# Power_Distribution_-_Solar_Sense_Telemet.net
KiCad netlist of a schematic drawn in Altium Designer
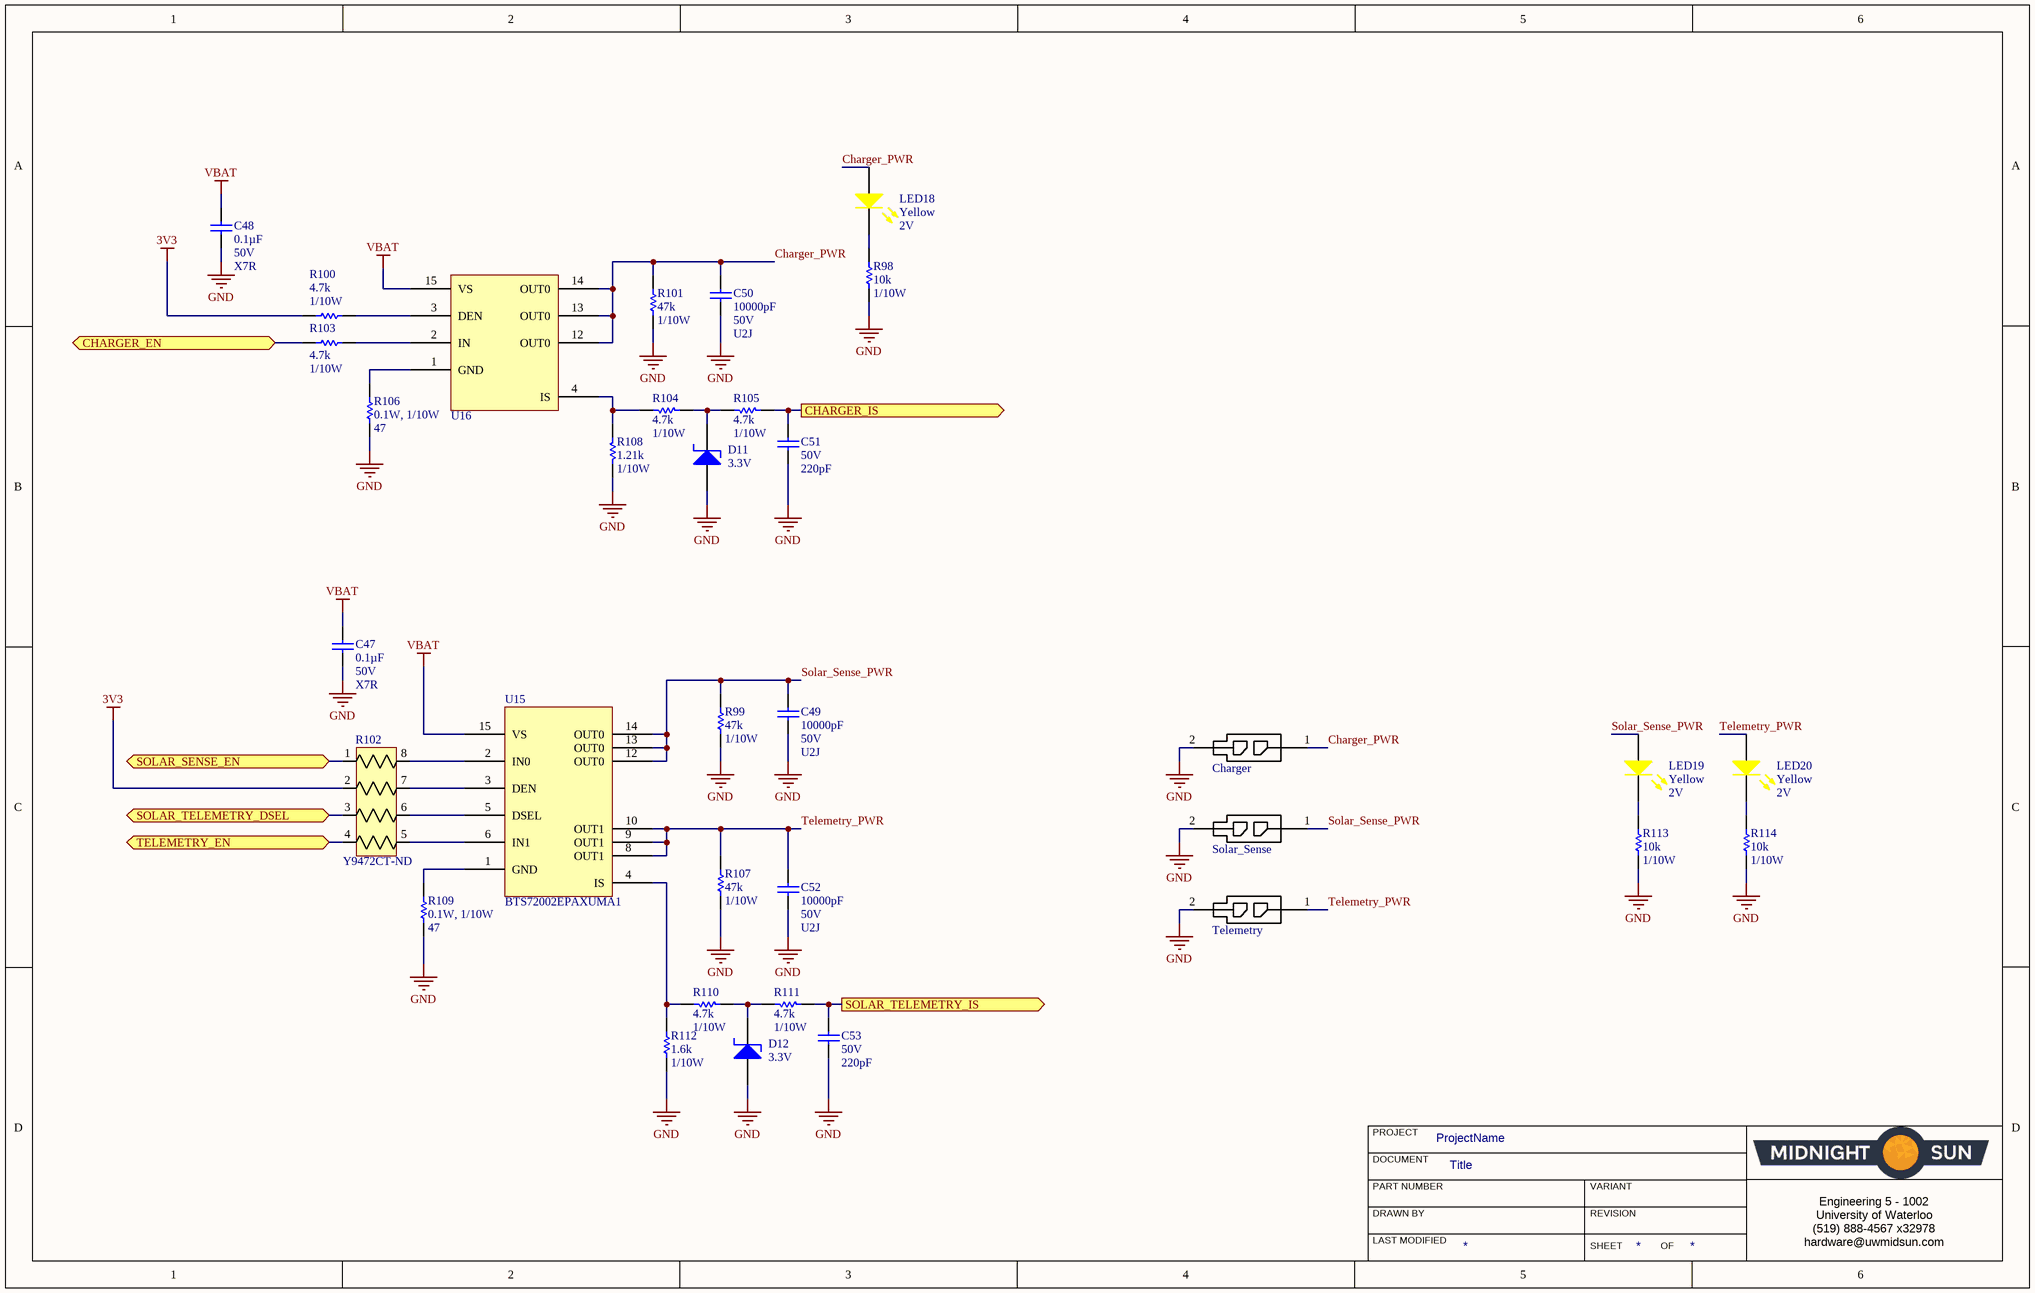
[diagram p0: Power Distribution - Solar Sense, Telemetry, and Charger.SchDoc]

(export (version "E")
  (design (tool "Eeschema 10.0.6"))
  (components
    (comp (ref "C47")
      (value "CAP CER 0.1UF 50V 10% X7R 0603")
      (footprint "CAP, 0603")
      (description "0.10µF ±10% 50V Ceramic Capacitor X7R 0603 (1608 Metric)")
      (fields
        (field (name "TOLERANCE") "±10%")
        (field (name "CAPACITANCE") "0.1µF")
        (field (name "VOLTAGE") "50V")
        (field (name "TEMPERATURE COEFFICIENT") "X7R")
      )
      (libsource (lib "Schematic Diagrams") (part "CAP CER 0.1UF 50V 10% X7R 0603"))
    )
    (comp (ref "C48")
      (value "CAP CER 0.1UF 50V 10% X7R 0603")
      (footprint "CAP, 0603")
      (description "0.10µF ±10% 50V Ceramic Capacitor X7R 0603 (1608 Metric)")
      (fields
        (field (name "TOLERANCE") "±10%")
        (field (name "CAPACITANCE") "0.1µF")
        (field (name "VOLTAGE") "50V")
        (field (name "TEMPERATURE COEFFICIENT") "X7R")
      )
      (libsource (lib "Schematic Diagrams") (part "CAP CER 0.1UF 50V 10% X7R 0603"))
    )
    (comp (ref "C49")
      (value "CAP CER 10nF 50V 5% X7R 0603")
      (footprint "CAP, 0603")
      (description "10000pF ±5% 50V Ceramic Capacitor U2J 0603 (1608 Metric)")
      (fields
        (field (name "TOLERANCE") "±5%")
        (field (name "CAPACITANCE") "10000pF")
        (field (name "VOLTAGE") "50V")
        (field (name "TEMPERATURE COEFFICIENT") "U2J")
      )
      (libsource (lib "Schematic Diagrams") (part "CAP CER 10nF 50V 5% X7R 0603"))
    )
    (comp (ref "C50")
      (value "CAP CER 10nF 50V 5% X7R 0603")
      (footprint "CAP, 0603")
      (description "10000pF ±5% 50V Ceramic Capacitor U2J 0603 (1608 Metric)")
      (fields
        (field (name "TOLERANCE") "±5%")
        (field (name "CAPACITANCE") "10000pF")
        (field (name "VOLTAGE") "50V")
        (field (name "TEMPERATURE COEFFICIENT") "U2J")
      )
      (libsource (lib "Schematic Diagrams") (part "CAP CER 10nF 50V 5% X7R 0603"))
    )
    (comp (ref "C51")
      (value "CAP CER 220PF 50V C0G/NP0 0603")
      (footprint "CAP, 0603")
      (description "220pF ±5% 50V Ceramic Capacitor C0G, NP0 0603 (1608 Metric)")
      (fields
        (field (name "MANUFACTURER") "KEMET")
        (field (name "TOLERANCE") "5%")
        (field (name "VOLTAGE RATING") "50V")
        (field (name "CAPACITANCE") "220pF")
      )
      (libsource (lib "Schematic Diagrams") (part "CAP CER 220PF 50V C0G/NP0 0603"))
    )
    (comp (ref "C52")
      (value "CAP CER 10nF 50V 5% X7R 0603")
      (footprint "CAP, 0603")
      (description "10000pF ±5% 50V Ceramic Capacitor U2J 0603 (1608 Metric)")
      (fields
        (field (name "TOLERANCE") "±5%")
        (field (name "CAPACITANCE") "10000pF")
        (field (name "VOLTAGE") "50V")
        (field (name "TEMPERATURE COEFFICIENT") "U2J")
      )
      (libsource (lib "Schematic Diagrams") (part "CAP CER 10nF 50V 5% X7R 0603"))
    )
    (comp (ref "C53")
      (value "CAP CER 220PF 50V C0G/NP0 0603")
      (footprint "CAP, 0603")
      (description "220pF ±5% 50V Ceramic Capacitor C0G, NP0 0603 (1608 Metric)")
      (fields
        (field (name "MANUFACTURER") "KEMET")
        (field (name "TOLERANCE") "5%")
        (field (name "VOLTAGE RATING") "50V")
        (field (name "CAPACITANCE") "220pF")
      )
      (libsource (lib "Schematic Diagrams") (part "CAP CER 220PF 50V C0G/NP0 0603"))
    )
    (comp (ref "Charger")
      (value "CONN 2POS MICRO-FIT 3mm")
      (footprint "CONN, 2POS MICRO-FIT")
      (description "Connector Header Through Hole 2 position")
      (fields (field (name "MANUFACTURER") "Molex") (field (name "MANUFACTURER PART NUMBER") "43045-0227"))
      (libsource (lib "Schematic Diagrams") (part "CONN 2POS MICRO-FIT 3mm"))
    )
    (comp (ref "D11")
      (value "DIODE ZENER 3.3V 200MW SOD323")
      (footprint "sod-323")
      (description "Zener Diode 3.3V 200mW ±5% Surface Mount SOD-323")
      (fields (field (name "VOLTAGE") "3.3V"))
      (libsource (lib "Schematic Diagrams") (part "DIODE ZENER 3.3V 200MW SOD323"))
    )
    (comp (ref "D12")
      (value "DIODE ZENER 3.3V 200MW SOD323")
      (footprint "sod-323")
      (description "Zener Diode 3.3V 200mW ±5% Surface Mount SOD-323")
      (fields (field (name "VOLTAGE") "3.3V"))
      (libsource (lib "Schematic Diagrams") (part "DIODE ZENER 3.3V 200MW SOD323"))
    )
    (comp (ref "LED18")
      (value "LED YELLOW CLEAR 2.1V 0603")
      (footprint "LED_0603")
      (description "Yellow 590nm LED Indication - Discrete 2V 0603 (1608 Metric)")
      (fields
        (field (name "MANUFACTURER") "Wurth Electronics Inc.")
        (field (name "MANUFACTURER PART NUMBER") "150060YS75000")
        (field (name "COLOR") "Yellow")
        (field (name "VOLTAGE - FORWARD (VF) (TYP)") "2V")
      )
      (libsource (lib "Schematic Diagrams") (part "LED YELLOW CLEAR 2.1V 0603"))
    )
    (comp (ref "LED19")
      (value "LED YELLOW CLEAR 2.1V 0603")
      (footprint "LED_0603")
      (description "Yellow 590nm LED Indication - Discrete 2V 0603 (1608 Metric)")
      (fields
        (field (name "MANUFACTURER") "Wurth Electronics Inc.")
        (field (name "MANUFACTURER PART NUMBER") "150060YS75000")
        (field (name "COLOR") "Yellow")
        (field (name "VOLTAGE - FORWARD (VF) (TYP)") "2V")
      )
      (libsource (lib "Schematic Diagrams") (part "LED YELLOW CLEAR 2.1V 0603"))
    )
    (comp (ref "LED20")
      (value "LED YELLOW CLEAR 2.1V 0603")
      (footprint "LED_0603")
      (description "Yellow 590nm LED Indication - Discrete 2V 0603 (1608 Metric)")
      (fields
        (field (name "MANUFACTURER") "Wurth Electronics Inc.")
        (field (name "MANUFACTURER PART NUMBER") "150060YS75000")
        (field (name "COLOR") "Yellow")
        (field (name "VOLTAGE - FORWARD (VF) (TYP)") "2V")
      )
      (libsource (lib "Schematic Diagrams") (part "LED YELLOW CLEAR 2.1V 0603"))
    )
    (comp (ref "R98")
      (value "RES 10K OHM 1% 1/10W 0603")
      (footprint "RES, 0603")
      (description "RES SMD 10K OHM 1% 1/10W 0603")
      (fields
        (field (name "TOLERANCE") "±1%")
        (field (name "RESISTANCE") "10k")
        (field (name "POWER") "1/10W")
      )
      (libsource (lib "Schematic Diagrams") (part "RES 10K OHM 1% 1/10W 0603"))
    )
    (comp (ref "R99")
      (value "RES 47K OHM 1% 1/10W 0603")
      (footprint "RES, 0603")
      (description "47 kOhms ±1% 0.1W, 1/10W Chip Resistor 0603 (1608 Metric) Automotive AEC-Q200 Thick Film")
      (fields
        (field (name "MANUFACTURER") "Panasonic")
        (field (name "MANUFACTURER PART NUMBER") "ERJ3EKF4702V")
        (field (name "RESISTANCE") "47k")
        (field (name "POWER RATING") "1/10W")
      )
      (libsource (lib "Schematic Diagrams") (part "RES 47K OHM 1% 1/10W 0603"))
    )
    (comp (ref "R100")
      (value "RES 4.7K OHM 1% 1/10W 0603")
      (footprint "RES, 0603")
      (description "4.7k Ohm ±1% 0.1W, 1/10W Chip Resistor 0603 (1608 Metric) Moisture Resistant Thick Film")
      (fields
        (field (name "TOLERANCE") "±1%")
        (field (name "RESISTANCE (OHMS)") "4.7k")
        (field (name "POWER (WATTS)") "1/10W")
      )
      (libsource (lib "Schematic Diagrams") (part "RES 4.7K OHM 1% 1/10W 0603"))
    )
    (comp (ref "R101")
      (value "RES 47K OHM 1% 1/10W 0603")
      (footprint "RES, 0603")
      (description "47 kOhms ±1% 0.1W, 1/10W Chip Resistor 0603 (1608 Metric) Automotive AEC-Q200 Thick Film")
      (fields
        (field (name "MANUFACTURER") "Panasonic")
        (field (name "MANUFACTURER PART NUMBER") "ERJ3EKF4702V")
        (field (name "RESISTANCE") "47k")
        (field (name "POWER RATING") "1/10W")
      )
      (libsource (lib "Schematic Diagrams") (part "RES 47K OHM 1% 1/10W 0603"))
    )
    (comp (ref "R102")
      (value "RES ARRAY 4 RES 4.7K OHM 1206")
      (footprint "RES ARRAY 4RES 1206")
      (fields (field (name "TOLERANCE") "±5%") (field (name "SUPPLIER PART NUMBER 1") "Y9472CT-ND"))
      (libsource (lib "Schematic Diagrams") (part "RES ARRAY 4 RES 4.7K OHM 1206"))
    )
    (comp (ref "R103")
      (value "RES 4.7K OHM 1% 1/10W 0603")
      (footprint "RES, 0603")
      (description "4.7k Ohm ±1% 0.1W, 1/10W Chip Resistor 0603 (1608 Metric) Moisture Resistant Thick Film")
      (fields
        (field (name "TOLERANCE") "±1%")
        (field (name "RESISTANCE (OHMS)") "4.7k")
        (field (name "POWER (WATTS)") "1/10W")
      )
      (libsource (lib "Schematic Diagrams") (part "RES 4.7K OHM 1% 1/10W 0603"))
    )
    (comp (ref "R104")
      (value "RES 4.7K OHM 1% 1/10W 0603")
      (footprint "RES, 0603")
      (description "4.7k Ohm ±1% 0.1W, 1/10W Chip Resistor 0603 (1608 Metric) Moisture Resistant Thick Film")
      (fields
        (field (name "TOLERANCE") "±1%")
        (field (name "RESISTANCE (OHMS)") "4.7k")
        (field (name "POWER (WATTS)") "1/10W")
      )
      (libsource (lib "Schematic Diagrams") (part "RES 4.7K OHM 1% 1/10W 0603"))
    )
    (comp (ref "R105")
      (value "RES 4.7K OHM 1% 1/10W 0603")
      (footprint "RES, 0603")
      (description "4.7k Ohm ±1% 0.1W, 1/10W Chip Resistor 0603 (1608 Metric) Moisture Resistant Thick Film")
      (fields
        (field (name "TOLERANCE") "±1%")
        (field (name "RESISTANCE (OHMS)") "4.7k")
        (field (name "POWER (WATTS)") "1/10W")
      )
      (libsource (lib "Schematic Diagrams") (part "RES 4.7K OHM 1% 1/10W 0603"))
    )
    (comp (ref "R106")
      (value "RES SMD 47 OHM 1% 1/10W 0603")
      (footprint "RES, 0603")
      (fields
        (field (name "TOLERANCE") "±1%")
        (field (name "POWER (WATTS)") "0.1W, 1/10W")
        (field (name "VALUES") "47")
      )
      (libsource (lib "Schematic Diagrams") (part "RES SMD 47 OHM 1% 1/10W 0603"))
    )
    (comp (ref "R107")
      (value "RES 47K OHM 1% 1/10W 0603")
      (footprint "RES, 0603")
      (description "47 kOhms ±1% 0.1W, 1/10W Chip Resistor 0603 (1608 Metric) Automotive AEC-Q200 Thick Film")
      (fields
        (field (name "MANUFACTURER") "Panasonic")
        (field (name "MANUFACTURER PART NUMBER") "ERJ3EKF4702V")
        (field (name "RESISTANCE") "47k")
        (field (name "POWER RATING") "1/10W")
      )
      (libsource (lib "Schematic Diagrams") (part "RES 47K OHM 1% 1/10W 0603"))
    )
    (comp (ref "R108")
      (value "RES 1.21K OHM 1% 1/10W 0603")
      (footprint "RES, 0603")
      (description "1.21k Ohm ±1% 0.1W, 1/10W Chip Resistor 0603 (1608 Metric) Moisture Resistant Thick Film")
      (fields
        (field (name "TOLERANCE") "±1%")
        (field (name "RESISTANCE") "1.21k")
        (field (name "POWER") "1/10W")
      )
      (libsource (lib "Schematic Diagrams") (part "RES 1.21K OHM 1% 1/10W 0603"))
    )
    (comp (ref "R109")
      (value "RES SMD 47 OHM 1% 1/10W 0603")
      (footprint "RES, 0603")
      (fields
        (field (name "TOLERANCE") "±1%")
        (field (name "POWER (WATTS)") "0.1W, 1/10W")
        (field (name "VALUES") "47")
      )
      (libsource (lib "Schematic Diagrams") (part "RES SMD 47 OHM 1% 1/10W 0603"))
    )
    (comp (ref "R110")
      (value "RES 4.7K OHM 1% 1/10W 0603")
      (footprint "RES, 0603")
      (description "4.7k Ohm ±1% 0.1W, 1/10W Chip Resistor 0603 (1608 Metric) Moisture Resistant Thick Film")
      (fields
        (field (name "TOLERANCE") "±1%")
        (field (name "RESISTANCE (OHMS)") "4.7k")
        (field (name "POWER (WATTS)") "1/10W")
      )
      (libsource (lib "Schematic Diagrams") (part "RES 4.7K OHM 1% 1/10W 0603"))
    )
    (comp (ref "R111")
      (value "RES 4.7K OHM 1% 1/10W 0603")
      (footprint "RES, 0603")
      (description "4.7k Ohm ±1% 0.1W, 1/10W Chip Resistor 0603 (1608 Metric) Moisture Resistant Thick Film")
      (fields
        (field (name "TOLERANCE") "±1%")
        (field (name "RESISTANCE (OHMS)") "4.7k")
        (field (name "POWER (WATTS)") "1/10W")
      )
      (libsource (lib "Schematic Diagrams") (part "RES 4.7K OHM 1% 1/10W 0603"))
    )
    (comp (ref "R112")
      (value "RES 1.6K OHM 1% 1/10W 0603")
      (footprint "RES, 0603")
      (description "1.6 kOhms ±1% 0.1W, 1/10W Chip Resistor 0603 (1608 Metric) Moisture Resistant Thick Film")
      (fields
        (field (name "MANUFACTURER") "Yageo")
        (field (name "MANUFACTURER PART NUMBER") "RC0603FR-071K6L")
        (field (name "RESISTANCE") "1.6k")
        (field (name "POWER RATING") "1/10W")
      )
      (libsource (lib "Schematic Diagrams") (part "RES 1.6K OHM 1% 1/10W 0603"))
    )
    (comp (ref "R113")
      (value "RES 10K OHM 1% 1/10W 0603")
      (footprint "RES, 0603")
      (description "RES SMD 10K OHM 1% 1/10W 0603")
      (fields
        (field (name "TOLERANCE") "±1%")
        (field (name "RESISTANCE") "10k")
        (field (name "POWER") "1/10W")
      )
      (libsource (lib "Schematic Diagrams") (part "RES 10K OHM 1% 1/10W 0603"))
    )
    (comp (ref "R114")
      (value "RES 10K OHM 1% 1/10W 0603")
      (footprint "RES, 0603")
      (description "RES SMD 10K OHM 1% 1/10W 0603")
      (fields
        (field (name "TOLERANCE") "±1%")
        (field (name "RESISTANCE") "10k")
        (field (name "POWER") "1/10W")
      )
      (libsource (lib "Schematic Diagrams") (part "RES 10K OHM 1% 1/10W 0603"))
    )
    (comp (ref "Solar_Sense")
      (value "CONN 2POS MICRO-FIT 3mm")
      (footprint "CONN, 2POS MICRO-FIT")
      (description "Connector Header Through Hole 2 position")
      (fields (field (name "MANUFACTURER") "Molex") (field (name "MANUFACTURER PART NUMBER") "43045-0227"))
      (libsource (lib "Schematic Diagrams") (part "CONN 2POS MICRO-FIT 3mm"))
    )
    (comp (ref "Telemetry")
      (value "CONN 2POS MICRO-FIT 3mm")
      (footprint "CONN, 2POS MICRO-FIT")
      (description "Connector Header Through Hole 2 position")
      (fields (field (name "MANUFACTURER") "Molex") (field (name "MANUFACTURER PART NUMBER") "43045-0227"))
      (libsource (lib "Schematic Diagrams") (part "CONN 2POS MICRO-FIT 3mm"))
    )
    (comp (ref "U15")
      (value "IC LOAD SWITCH BTS7200-2EPA PG-TSDSO-14_1")
      (footprint "IC LOAD SWITCH PG-TSDSO-14-22")
      (description "Power Switch/Driver 1:1 N-Channel 1.2A PG-TSDSO-14-22")
      (fields
        (field (name "MANUFACTURER") "Infineon")
        (field (name "MANUFACTURER PART NUMBER") "BTS72002EPAXUMA1")
      )
      (libsource (lib "Schematic Diagrams") (part "IC LOAD SWITCH BTS7200-2EPA PG-TSDSO-14_1"))
    )
    (comp (ref "U16")
      (value "IC LOAD SWITCH BTS70401EPA PG-TSDSO-14-22")
      (footprint "IC LOAD SWITCH PG-TSDSO-14-22")
      (description "Power Switch/Driver 1:1 N-Channel 4.5A PG-TSDSO-14-22")
      (fields
        (field (name "MANUFACTURER") "Infineon")
        (field (name "MANUFACTURER PART NUMBER") "BTS70401EPAXUMA1")
      )
      (libsource (lib "Schematic Diagrams") (part "IC LOAD SWITCH BTS70401EPA PG-TSDSO-14-22"))
    )
  )
  (nets
    (net (code "1") (name "/CHARGER_EN") (class "Default")
      (node (ref "R103") (pin "1") (pinfunction "1_1") (pintype "passive"))
    )
    (net (code "2") (name "/CHARGER_IS") (class "Default")
      (node (ref "C51") (pin "1") (pinfunction "1_1") (pintype "passive"))
      (node (ref "R105") (pin "1") (pinfunction "1_1") (pintype "passive"))
    )
    (net (code "3") (name "/Charger_PWR") (class "Default")
      (node (ref "C50") (pin "1") (pinfunction "1_1") (pintype "passive"))
      (node (ref "Charger") (pin "1") (pinfunction "1_1") (pintype "passive"))
      (node (ref "LED18") (pin "1") (pinfunction "A_1") (pintype "passive"))
      (node (ref "R101") (pin "1") (pinfunction "1_1") (pintype "passive"))
      (node (ref "U16") (pin "12") (pinfunction "OUT0_12") (pintype "passive"))
      (node (ref "U16") (pin "13") (pinfunction "OUT0_13") (pintype "passive"))
      (node (ref "U16") (pin "14") (pinfunction "OUT0_14") (pintype "passive"))
    )
    (net (code "4") (name "/SOLAR_SENSE_EN") (class "Default")
      (node (ref "R102") (pin "1") (pinfunction "1_1") (pintype "passive"))
    )
    (net (code "5") (name "/SOLAR_TELEMETRY_DSEL") (class "Default")
      (node (ref "R102") (pin "3") (pinfunction "3_3") (pintype "passive"))
    )
    (net (code "6") (name "/SOLAR_TELEMETRY_IS") (class "Default")
      (node (ref "C53") (pin "1") (pinfunction "1_1") (pintype "passive"))
      (node (ref "R111") (pin "1") (pinfunction "1_1") (pintype "passive"))
    )
    (net (code "7") (name "/Solar_Sense_PWR") (class "Default")
      (node (ref "C49") (pin "1") (pinfunction "1_1") (pintype "passive"))
      (node (ref "LED19") (pin "1") (pinfunction "A_1") (pintype "passive"))
      (node (ref "R99") (pin "1") (pinfunction "1_1") (pintype "passive"))
      (node (ref "Solar_Sense") (pin "1") (pinfunction "1_1") (pintype "passive"))
      (node (ref "U15") (pin "12") (pinfunction "OUT0_12") (pintype "passive"))
      (node (ref "U15") (pin "13") (pinfunction "OUT0_13") (pintype "passive"))
      (node (ref "U15") (pin "14") (pinfunction "OUT0_14") (pintype "passive"))
    )
    (net (code "8") (name "/TELEMETRY_EN") (class "Default")
      (node (ref "R102") (pin "4") (pinfunction "4_4") (pintype "passive"))
    )
    (net (code "9") (name "/Telemetry_PWR") (class "Default")
      (node (ref "C52") (pin "1") (pinfunction "1_1") (pintype "passive"))
      (node (ref "LED20") (pin "1") (pinfunction "A_1") (pintype "passive"))
      (node (ref "R107") (pin "1") (pinfunction "1_1") (pintype "passive"))
      (node (ref "Telemetry") (pin "1") (pinfunction "1_1") (pintype "passive"))
      (node (ref "U15") (pin "10") (pinfunction "OUT1_10") (pintype "passive"))
      (node (ref "U15") (pin "8") (pinfunction "OUT1_8") (pintype "passive"))
      (node (ref "U15") (pin "9") (pinfunction "OUT1_9") (pintype "passive"))
    )
    (net (code "10") (name "3V3") (class "Default")
      (node (ref "R100") (pin "1") (pinfunction "1_1") (pintype "passive"))
      (node (ref "R102") (pin "2") (pinfunction "2_2") (pintype "passive"))
    )
    (net (code "11") (name "GND") (class "Default")
      (node (ref "C47") (pin "2") (pinfunction "2_2") (pintype "passive"))
      (node (ref "C48") (pin "2") (pinfunction "2_2") (pintype "passive"))
      (node (ref "C49") (pin "2") (pinfunction "2_2") (pintype "passive"))
      (node (ref "C50") (pin "2") (pinfunction "2_2") (pintype "passive"))
      (node (ref "C51") (pin "2") (pinfunction "2_2") (pintype "passive"))
      (node (ref "C52") (pin "2") (pinfunction "2_2") (pintype "passive"))
      (node (ref "C53") (pin "2") (pinfunction "2_2") (pintype "passive"))
      (node (ref "Charger") (pin "2") (pinfunction "2_2") (pintype "passive"))
      (node (ref "D11") (pin "1") (pinfunction "A_1") (pintype "passive"))
      (node (ref "D12") (pin "1") (pinfunction "A_1") (pintype "passive"))
      (node (ref "R101") (pin "2") (pinfunction "2_2") (pintype "passive"))
      (node (ref "R106") (pin "2") (pinfunction "2_2") (pintype "passive"))
      (node (ref "R107") (pin "2") (pinfunction "2_2") (pintype "passive"))
      (node (ref "R108") (pin "2") (pinfunction "2_2") (pintype "passive"))
      (node (ref "R109") (pin "2") (pinfunction "2_2") (pintype "passive"))
      (node (ref "R112") (pin "2") (pinfunction "2_2") (pintype "passive"))
      (node (ref "R113") (pin "2") (pinfunction "2_2") (pintype "passive"))
      (node (ref "R114") (pin "2") (pinfunction "2_2") (pintype "passive"))
      (node (ref "R98") (pin "2") (pinfunction "2_2") (pintype "passive"))
      (node (ref "R99") (pin "2") (pinfunction "2_2") (pintype "passive"))
      (node (ref "Solar_Sense") (pin "2") (pinfunction "2_2") (pintype "passive"))
      (node (ref "Telemetry") (pin "2") (pinfunction "2_2") (pintype "passive"))
    )
    (net (code "12") (name "Net-(D11-K)") (class "Default")
      (node (ref "D11") (pin "2") (pinfunction "K_2") (pintype "passive"))
      (node (ref "R104") (pin "1") (pinfunction "1_1") (pintype "passive"))
      (node (ref "R105") (pin "2") (pinfunction "2_2") (pintype "passive"))
    )
    (net (code "13") (name "Net-(D12-K)") (class "Default")
      (node (ref "D12") (pin "2") (pinfunction "K_2") (pintype "passive"))
      (node (ref "R110") (pin "1") (pinfunction "1_1") (pintype "passive"))
      (node (ref "R111") (pin "2") (pinfunction "2_2") (pintype "passive"))
    )
    (net (code "14") (name "Net-(LED18-K)") (class "Default")
      (node (ref "LED18") (pin "2") (pinfunction "K_2") (pintype "passive"))
      (node (ref "R98") (pin "1") (pinfunction "1_1") (pintype "passive"))
    )
    (net (code "15") (name "Net-(LED19-K)") (class "Default")
      (node (ref "LED19") (pin "2") (pinfunction "K_2") (pintype "passive"))
      (node (ref "R113") (pin "1") (pinfunction "1_1") (pintype "passive"))
    )
    (net (code "16") (name "Net-(LED20-K)") (class "Default")
      (node (ref "LED20") (pin "2") (pinfunction "K_2") (pintype "passive"))
      (node (ref "R114") (pin "1") (pinfunction "1_1") (pintype "passive"))
    )
    (net (code "17") (name "Net-(U15-DEN)") (class "Default")
      (node (ref "R102") (pin "7") (pinfunction "7_7") (pintype "passive"))
      (node (ref "U15") (pin "3") (pinfunction "DEN_3") (pintype "passive"))
    )
    (net (code "18") (name "Net-(U15-DSEL)") (class "Default")
      (node (ref "R102") (pin "6") (pinfunction "6_6") (pintype "passive"))
      (node (ref "U15") (pin "5") (pinfunction "DSEL_5") (pintype "passive"))
    )
    (net (code "19") (name "Net-(U15-GND)") (class "Default")
      (node (ref "R109") (pin "1") (pinfunction "1_1") (pintype "passive"))
      (node (ref "U15") (pin "1") (pinfunction "GND_1") (pintype "passive"))
    )
    (net (code "20") (name "Net-(U15-IN0)") (class "Default")
      (node (ref "R102") (pin "8") (pinfunction "8_8") (pintype "passive"))
      (node (ref "U15") (pin "2") (pinfunction "IN0_2") (pintype "passive"))
    )
    (net (code "21") (name "Net-(U15-IN1)") (class "Default")
      (node (ref "R102") (pin "5") (pinfunction "5_5") (pintype "passive"))
      (node (ref "U15") (pin "6") (pinfunction "IN1_6") (pintype "passive"))
    )
    (net (code "22") (name "Net-(U15-IS)") (class "Default")
      (node (ref "R110") (pin "2") (pinfunction "2_2") (pintype "passive"))
      (node (ref "R112") (pin "1") (pinfunction "1_1") (pintype "passive"))
      (node (ref "U15") (pin "4") (pinfunction "IS_4") (pintype "passive"))
    )
    (net (code "23") (name "Net-(U16-DEN)") (class "Default")
      (node (ref "R100") (pin "2") (pinfunction "2_2") (pintype "passive"))
      (node (ref "U16") (pin "3") (pinfunction "DEN_3") (pintype "passive"))
    )
    (net (code "24") (name "Net-(U16-GND)") (class "Default")
      (node (ref "R106") (pin "1") (pinfunction "1_1") (pintype "passive"))
      (node (ref "U16") (pin "1") (pinfunction "GND_1") (pintype "passive"))
    )
    (net (code "25") (name "Net-(U16-IN)") (class "Default")
      (node (ref "R103") (pin "2") (pinfunction "2_2") (pintype "passive"))
      (node (ref "U16") (pin "2") (pinfunction "IN_2") (pintype "passive"))
    )
    (net (code "26") (name "Net-(U16-IS)") (class "Default")
      (node (ref "R104") (pin "2") (pinfunction "2_2") (pintype "passive"))
      (node (ref "R108") (pin "1") (pinfunction "1_1") (pintype "passive"))
      (node (ref "U16") (pin "4") (pinfunction "IS_4") (pintype "passive"))
    )
    (net (code "27") (name "VBAT") (class "Default")
      (node (ref "C47") (pin "1") (pinfunction "1_1") (pintype "passive"))
      (node (ref "C48") (pin "1") (pinfunction "1_1") (pintype "passive"))
      (node (ref "U15") (pin "15") (pinfunction "VS_15") (pintype "passive"))
      (node (ref "U16") (pin "15") (pinfunction "VS_15") (pintype "passive"))
    )
  )
)
